# CW340_USERIO_Breakout.net
KiCad netlist of a schematic drawn in Altium Designer
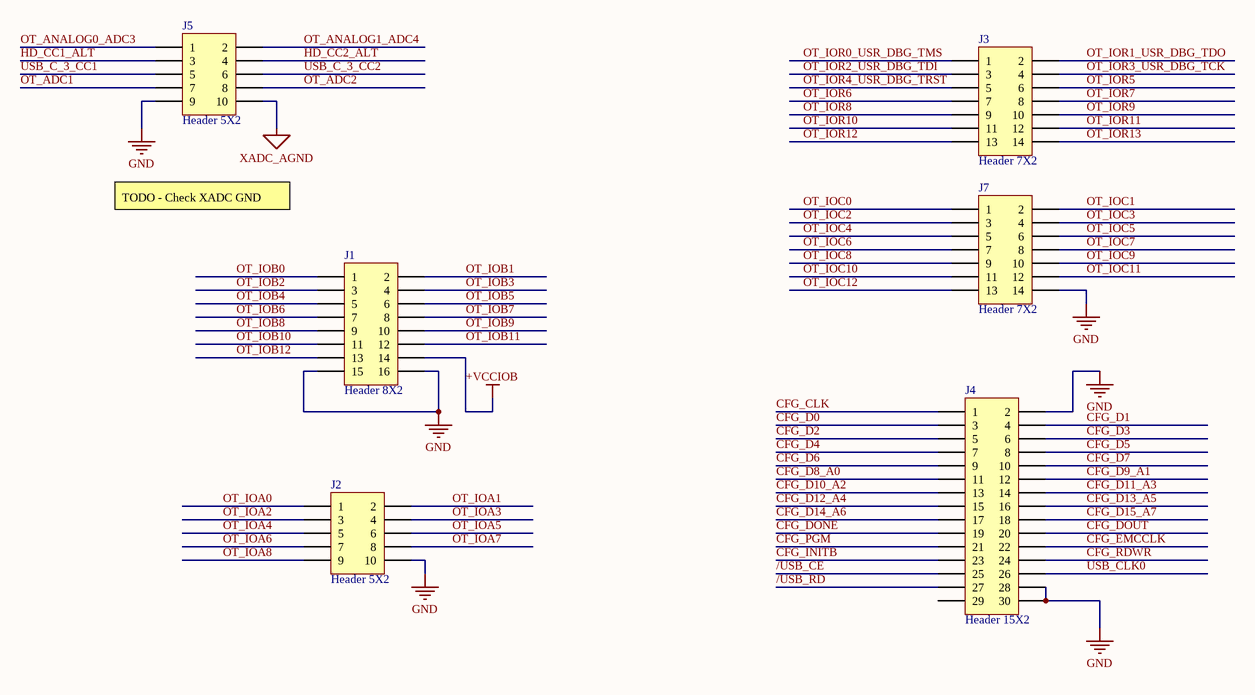
[diagram p0: CW340_USERIO_Breakout.SchDoc]

(export (version "E")
  (design (tool "Eeschema 10.0.6"))
  (components
    (comp (ref "J1")
      (value "Header 8X2")
      (footprint "HDR2X8")
      (description "Header, 8-Pin, Dual row")
      (fields (field (name "PUBLISHER") "Altium Limited"))
      (libsource (lib "Miscellaneous Connectors") (part "Header 8X2"))
    )
    (comp (ref "J2")
      (value "Header 5X2")
      (footprint "HDR2X5")
      (description "Header, 5-Pin, Dual row")
      (fields (field (name "PUBLISHER") "Altium Limited"))
      (libsource (lib "Miscellaneous Connectors") (part "Header 5X2"))
    )
    (comp (ref "J3")
      (value "Header 7X2")
      (footprint "HDR2X7")
      (description "Header, 7-Pin, Dual row")
      (fields (field (name "PUBLISHER") "Altium Limited"))
      (libsource (lib "Miscellaneous Connectors") (part "Header 7X2"))
    )
    (comp (ref "J4")
      (value "Header 15X2")
      (footprint "HDR2X15")
      (description "Header, 15-Pin, Dual row")
      (fields (field (name "PUBLISHER") "Altium Limited"))
      (libsource (lib "Miscellaneous Connectors") (part "Header 15X2"))
    )
    (comp (ref "J5")
      (value "Header 5X2")
      (footprint "HDR2X5")
      (description "Header, 5-Pin, Dual row")
      (fields (field (name "PUBLISHER") "Altium Limited"))
      (libsource (lib "Miscellaneous Connectors") (part "Header 5X2"))
    )
    (comp (ref "J7")
      (value "Header 7X2")
      (footprint "HDR2X7")
      (description "Header, 7-Pin, Dual row")
      (fields (field (name "PUBLISHER") "Altium Limited"))
      (libsource (lib "Miscellaneous Connectors") (part "Header 7X2"))
    )
  )
  (nets
    (net (code "1") (name "+VCCIOB") (class "Default")
      (node (ref "J1") (pin "14") (pinfunction "14_14") (pintype "passive"))
    )
    (net (code "2") (name "/CFG_CLK") (class "Default")
      (node (ref "J4") (pin "1") (pinfunction "1_1") (pintype "passive"))
    )
    (net (code "3") (name "/CFG_D0") (class "Default")
      (node (ref "J4") (pin "3") (pinfunction "3_3") (pintype "passive"))
    )
    (net (code "4") (name "/CFG_D1") (class "Default")
      (node (ref "J4") (pin "4") (pinfunction "4_4") (pintype "passive"))
    )
    (net (code "5") (name "/CFG_D2") (class "Default")
      (node (ref "J4") (pin "5") (pinfunction "5_5") (pintype "passive"))
    )
    (net (code "6") (name "/CFG_D3") (class "Default")
      (node (ref "J4") (pin "6") (pinfunction "6_6") (pintype "passive"))
    )
    (net (code "7") (name "/CFG_D4") (class "Default")
      (node (ref "J4") (pin "7") (pinfunction "7_7") (pintype "passive"))
    )
    (net (code "8") (name "/CFG_D5") (class "Default")
      (node (ref "J4") (pin "8") (pinfunction "8_8") (pintype "passive"))
    )
    (net (code "9") (name "/CFG_D6") (class "Default")
      (node (ref "J4") (pin "9") (pinfunction "9_9") (pintype "passive"))
    )
    (net (code "10") (name "/CFG_D7") (class "Default")
      (node (ref "J4") (pin "10") (pinfunction "10_10") (pintype "passive"))
    )
    (net (code "11") (name "/CFG_D8_A0") (class "Default")
      (node (ref "J4") (pin "11") (pinfunction "11_11") (pintype "passive"))
    )
    (net (code "12") (name "/CFG_D9_A1") (class "Default")
      (node (ref "J4") (pin "12") (pinfunction "12_12") (pintype "passive"))
    )
    (net (code "13") (name "/CFG_D10_A2") (class "Default")
      (node (ref "J4") (pin "13") (pinfunction "13_13") (pintype "passive"))
    )
    (net (code "14") (name "/CFG_D11_A3") (class "Default")
      (node (ref "J4") (pin "14") (pinfunction "14_14") (pintype "passive"))
    )
    (net (code "15") (name "/CFG_D12_A4") (class "Default")
      (node (ref "J4") (pin "15") (pinfunction "15_15") (pintype "passive"))
    )
    (net (code "16") (name "/CFG_D13_A5") (class "Default")
      (node (ref "J4") (pin "16") (pinfunction "16_16") (pintype "passive"))
    )
    (net (code "17") (name "/CFG_D14_A6") (class "Default")
      (node (ref "J4") (pin "17") (pinfunction "17_17") (pintype "passive"))
    )
    (net (code "18") (name "/CFG_D15_A7") (class "Default")
      (node (ref "J4") (pin "18") (pinfunction "18_18") (pintype "passive"))
    )
    (net (code "19") (name "/CFG_DONE") (class "Default")
      (node (ref "J4") (pin "19") (pinfunction "19_19") (pintype "passive"))
    )
    (net (code "20") (name "/CFG_DOUT") (class "Default")
      (node (ref "J4") (pin "20") (pinfunction "20_20") (pintype "passive"))
    )
    (net (code "21") (name "/CFG_EMCCLK") (class "Default")
      (node (ref "J4") (pin "22") (pinfunction "22_22") (pintype "passive"))
    )
    (net (code "22") (name "/CFG_INITB") (class "Default")
      (node (ref "J4") (pin "23") (pinfunction "23_23") (pintype "passive"))
    )
    (net (code "23") (name "/CFG_PGM") (class "Default")
      (node (ref "J4") (pin "21") (pinfunction "21_21") (pintype "passive"))
    )
    (net (code "24") (name "/CFG_RDWR") (class "Default")
      (node (ref "J4") (pin "24") (pinfunction "24_24") (pintype "passive"))
    )
    (net (code "25") (name "/HD_CC1_ALT") (class "Default")
      (node (ref "J5") (pin "3") (pinfunction "3_3") (pintype "passive"))
    )
    (net (code "26") (name "/HD_CC2_ALT") (class "Default")
      (node (ref "J5") (pin "4") (pinfunction "4_4") (pintype "passive"))
    )
    (net (code "27") (name "/OT_ADC1") (class "Default")
      (node (ref "J5") (pin "7") (pinfunction "7_7") (pintype "passive"))
    )
    (net (code "28") (name "/OT_ADC2") (class "Default")
      (node (ref "J5") (pin "8") (pinfunction "8_8") (pintype "passive"))
    )
    (net (code "29") (name "/OT_ANALOG0_ADC3") (class "Default")
      (node (ref "J5") (pin "1") (pinfunction "1_1") (pintype "passive"))
    )
    (net (code "30") (name "/OT_ANALOG1_ADC4") (class "Default")
      (node (ref "J5") (pin "2") (pinfunction "2_2") (pintype "passive"))
    )
    (net (code "31") (name "/OT_IOA0") (class "Default")
      (node (ref "J2") (pin "1") (pinfunction "1_1") (pintype "passive"))
    )
    (net (code "32") (name "/OT_IOA1") (class "Default")
      (node (ref "J2") (pin "2") (pinfunction "2_2") (pintype "passive"))
    )
    (net (code "33") (name "/OT_IOA2") (class "Default")
      (node (ref "J2") (pin "3") (pinfunction "3_3") (pintype "passive"))
    )
    (net (code "34") (name "/OT_IOA3") (class "Default")
      (node (ref "J2") (pin "4") (pinfunction "4_4") (pintype "passive"))
    )
    (net (code "35") (name "/OT_IOA4") (class "Default")
      (node (ref "J2") (pin "5") (pinfunction "5_5") (pintype "passive"))
    )
    (net (code "36") (name "/OT_IOA5") (class "Default")
      (node (ref "J2") (pin "6") (pinfunction "6_6") (pintype "passive"))
    )
    (net (code "37") (name "/OT_IOA6") (class "Default")
      (node (ref "J2") (pin "7") (pinfunction "7_7") (pintype "passive"))
    )
    (net (code "38") (name "/OT_IOA7") (class "Default")
      (node (ref "J2") (pin "8") (pinfunction "8_8") (pintype "passive"))
    )
    (net (code "39") (name "/OT_IOA8") (class "Default")
      (node (ref "J2") (pin "9") (pinfunction "9_9") (pintype "passive"))
    )
    (net (code "40") (name "/OT_IOB0") (class "Default")
      (node (ref "J1") (pin "1") (pinfunction "1_1") (pintype "passive"))
    )
    (net (code "41") (name "/OT_IOB1") (class "Default")
      (node (ref "J1") (pin "2") (pinfunction "2_2") (pintype "passive"))
    )
    (net (code "42") (name "/OT_IOB2") (class "Default")
      (node (ref "J1") (pin "3") (pinfunction "3_3") (pintype "passive"))
    )
    (net (code "43") (name "/OT_IOB3") (class "Default")
      (node (ref "J1") (pin "4") (pinfunction "4_4") (pintype "passive"))
    )
    (net (code "44") (name "/OT_IOB4") (class "Default")
      (node (ref "J1") (pin "5") (pinfunction "5_5") (pintype "passive"))
    )
    (net (code "45") (name "/OT_IOB5") (class "Default")
      (node (ref "J1") (pin "6") (pinfunction "6_6") (pintype "passive"))
    )
    (net (code "46") (name "/OT_IOB6") (class "Default")
      (node (ref "J1") (pin "7") (pinfunction "7_7") (pintype "passive"))
    )
    (net (code "47") (name "/OT_IOB7") (class "Default")
      (node (ref "J1") (pin "8") (pinfunction "8_8") (pintype "passive"))
    )
    (net (code "48") (name "/OT_IOB8") (class "Default")
      (node (ref "J1") (pin "9") (pinfunction "9_9") (pintype "passive"))
    )
    (net (code "49") (name "/OT_IOB9") (class "Default")
      (node (ref "J1") (pin "10") (pinfunction "10_10") (pintype "passive"))
    )
    (net (code "50") (name "/OT_IOB10") (class "Default")
      (node (ref "J1") (pin "11") (pinfunction "11_11") (pintype "passive"))
    )
    (net (code "51") (name "/OT_IOB11") (class "Default")
      (node (ref "J1") (pin "12") (pinfunction "12_12") (pintype "passive"))
    )
    (net (code "52") (name "/OT_IOB12") (class "Default")
      (node (ref "J1") (pin "13") (pinfunction "13_13") (pintype "passive"))
    )
    (net (code "53") (name "/OT_IOC0") (class "Default")
      (node (ref "J7") (pin "1") (pinfunction "1_1") (pintype "passive"))
    )
    (net (code "54") (name "/OT_IOC1") (class "Default")
      (node (ref "J7") (pin "2") (pinfunction "2_2") (pintype "passive"))
    )
    (net (code "55") (name "/OT_IOC2") (class "Default")
      (node (ref "J7") (pin "3") (pinfunction "3_3") (pintype "passive"))
    )
    (net (code "56") (name "/OT_IOC3") (class "Default")
      (node (ref "J7") (pin "4") (pinfunction "4_4") (pintype "passive"))
    )
    (net (code "57") (name "/OT_IOC4") (class "Default")
      (node (ref "J7") (pin "5") (pinfunction "5_5") (pintype "passive"))
    )
    (net (code "58") (name "/OT_IOC5") (class "Default")
      (node (ref "J7") (pin "6") (pinfunction "6_6") (pintype "passive"))
    )
    (net (code "59") (name "/OT_IOC6") (class "Default")
      (node (ref "J7") (pin "7") (pinfunction "7_7") (pintype "passive"))
    )
    (net (code "60") (name "/OT_IOC7") (class "Default")
      (node (ref "J7") (pin "8") (pinfunction "8_8") (pintype "passive"))
    )
    (net (code "61") (name "/OT_IOC8") (class "Default")
      (node (ref "J7") (pin "9") (pinfunction "9_9") (pintype "passive"))
    )
    (net (code "62") (name "/OT_IOC9") (class "Default")
      (node (ref "J7") (pin "10") (pinfunction "10_10") (pintype "passive"))
    )
    (net (code "63") (name "/OT_IOC10") (class "Default")
      (node (ref "J7") (pin "11") (pinfunction "11_11") (pintype "passive"))
    )
    (net (code "64") (name "/OT_IOC11") (class "Default")
      (node (ref "J7") (pin "12") (pinfunction "12_12") (pintype "passive"))
    )
    (net (code "65") (name "/OT_IOC12") (class "Default")
      (node (ref "J7") (pin "13") (pinfunction "13_13") (pintype "passive"))
    )
    (net (code "66") (name "/OT_IOR0_USR_DBG_TMS") (class "Default")
      (node (ref "J3") (pin "1") (pinfunction "1_1") (pintype "passive"))
    )
    (net (code "67") (name "/OT_IOR1_USR_DBG_TDO") (class "Default")
      (node (ref "J3") (pin "2") (pinfunction "2_2") (pintype "passive"))
    )
    (net (code "68") (name "/OT_IOR2_USR_DBG_TDI") (class "Default")
      (node (ref "J3") (pin "3") (pinfunction "3_3") (pintype "passive"))
    )
    (net (code "69") (name "/OT_IOR3_USR_DBG_TCK") (class "Default")
      (node (ref "J3") (pin "4") (pinfunction "4_4") (pintype "passive"))
    )
    (net (code "70") (name "/OT_IOR4_USR_DBG_TRST") (class "Default")
      (node (ref "J3") (pin "5") (pinfunction "5_5") (pintype "passive"))
    )
    (net (code "71") (name "/OT_IOR5") (class "Default")
      (node (ref "J3") (pin "6") (pinfunction "6_6") (pintype "passive"))
    )
    (net (code "72") (name "/OT_IOR6") (class "Default")
      (node (ref "J3") (pin "7") (pinfunction "7_7") (pintype "passive"))
    )
    (net (code "73") (name "/OT_IOR7") (class "Default")
      (node (ref "J3") (pin "8") (pinfunction "8_8") (pintype "passive"))
    )
    (net (code "74") (name "/OT_IOR8") (class "Default")
      (node (ref "J3") (pin "9") (pinfunction "9_9") (pintype "passive"))
    )
    (net (code "75") (name "/OT_IOR9") (class "Default")
      (node (ref "J3") (pin "10") (pinfunction "10_10") (pintype "passive"))
    )
    (net (code "76") (name "/OT_IOR10") (class "Default")
      (node (ref "J3") (pin "11") (pinfunction "11_11") (pintype "passive"))
    )
    (net (code "77") (name "/OT_IOR11") (class "Default")
      (node (ref "J3") (pin "12") (pinfunction "12_12") (pintype "passive"))
    )
    (net (code "78") (name "/OT_IOR12") (class "Default")
      (node (ref "J3") (pin "13") (pinfunction "13_13") (pintype "passive"))
    )
    (net (code "79") (name "/OT_IOR13") (class "Default")
      (node (ref "J3") (pin "14") (pinfunction "14_14") (pintype "passive"))
    )
    (net (code "80") (name "/USB_CLK0") (class "Default")
      (node (ref "J4") (pin "26") (pinfunction "26_26") (pintype "passive"))
    )
    (net (code "81") (name "/USB_C_3_CC1") (class "Default")
      (node (ref "J5") (pin "5") (pinfunction "5_5") (pintype "passive"))
    )
    (net (code "82") (name "/USB_C_3_CC2") (class "Default")
      (node (ref "J5") (pin "6") (pinfunction "6_6") (pintype "passive"))
    )
    (net (code "83") (name "/{slash}USB_CE") (class "Default")
      (node (ref "J4") (pin "25") (pinfunction "25_25") (pintype "passive"))
    )
    (net (code "84") (name "/{slash}USB_RD") (class "Default")
      (node (ref "J4") (pin "27") (pinfunction "27_27") (pintype "passive"))
    )
    (net (code "85") (name "GND") (class "Default")
      (node (ref "J1") (pin "15") (pinfunction "15_15") (pintype "passive"))
      (node (ref "J1") (pin "16") (pinfunction "16_16") (pintype "passive"))
      (node (ref "J2") (pin "10") (pinfunction "10_10") (pintype "passive"))
      (node (ref "J4") (pin "2") (pinfunction "2_2") (pintype "passive"))
      (node (ref "J4") (pin "28") (pinfunction "28_28") (pintype "passive"))
      (node (ref "J4") (pin "30") (pinfunction "30_30") (pintype "passive"))
      (node (ref "J5") (pin "9") (pinfunction "9_9") (pintype "passive"))
      (node (ref "J7") (pin "14") (pinfunction "14_14") (pintype "passive"))
    )
    (net (code "86") (name "XADC_AGND") (class "Default")
      (node (ref "J5") (pin "10") (pinfunction "10_10") (pintype "passive"))
    )
    (net (code "87") (name "unconnected-(J4-Pad29)") (class "Default")
      (node (ref "J4") (pin "29") (pinfunction "29_29") (pintype "passive"))
    )
  )
)
